# Interface.net
KiCad netlist of a schematic drawn in Altium Designer
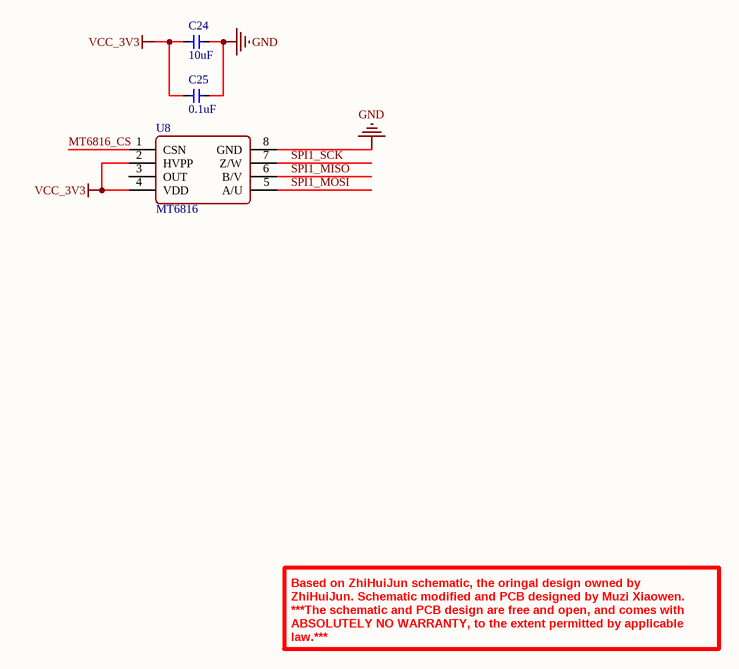
[diagram p0: Interface.SchDoc]

(export (version "E")
  (design (tool "Eeschema 10.0.6"))
  (components
    (comp (ref "C24")
      (value "10uF")
      (footprint "CAP_0402")
      (description "Capacitor")
      (libsource (lib "MyPcbLib") (part "电容-0402"))
    )
    (comp (ref "C25")
      (value "0.1uF")
      (footprint "motor42-lib:CAP_0402")
      (description "Capacitor")
      (libsource (lib "MyPcbLib") (part "电容-0402"))
    )
    (comp (ref "U8")
      (value "MT6816")
      (footprint "SO-8")
      (description "Magnetic Position Sensor")
      (libsource (lib "MyPcbLib") (part "MT6816"))
    )
  )
  (nets
    (net (code "1") (name "/MT6816_CS") (class "Default")
      (node (ref "U8") (pin "1") (pinfunction "CSN_1") (pintype "passive"))
    )
    (net (code "2") (name "/SPI1_MISO") (class "Default")
      (node (ref "U8") (pin "6") (pinfunction "B/V_6") (pintype "passive"))
    )
    (net (code "3") (name "/SPI1_MOSI") (class "Default")
      (node (ref "U8") (pin "5") (pinfunction "A/U_5") (pintype "passive"))
    )
    (net (code "4") (name "/SPI1_SCK") (class "Default")
      (node (ref "U8") (pin "7") (pinfunction "Z/W_7") (pintype "passive"))
    )
    (net (code "5") (name "GND") (class "Default")
      (node (ref "C24") (pin "1") (pinfunction "1_1") (pintype "passive"))
      (node (ref "C25") (pin "1") (pinfunction "1_1") (pintype "passive"))
      (node (ref "U8") (pin "8") (pinfunction "GND_8") (pintype "passive"))
    )
    (net (code "6") (name "VCC_3V3") (class "Default")
      (node (ref "C24") (pin "2") (pinfunction "2_2") (pintype "passive"))
      (node (ref "C25") (pin "2") (pinfunction "2_2") (pintype "passive"))
      (node (ref "U8") (pin "2") (pinfunction "HVPP_2") (pintype "passive"))
      (node (ref "U8") (pin "4") (pinfunction "VDD_4") (pintype "passive"))
    )
    (net (code "7") (name "unconnected-(U8-OUT-Pad3)") (class "Default")
      (node (ref "U8") (pin "3") (pinfunction "OUT_3") (pintype "passive"))
    )
  )
)
